# 06-LORA.net
KiCad netlist of a schematic drawn in Altium Designer
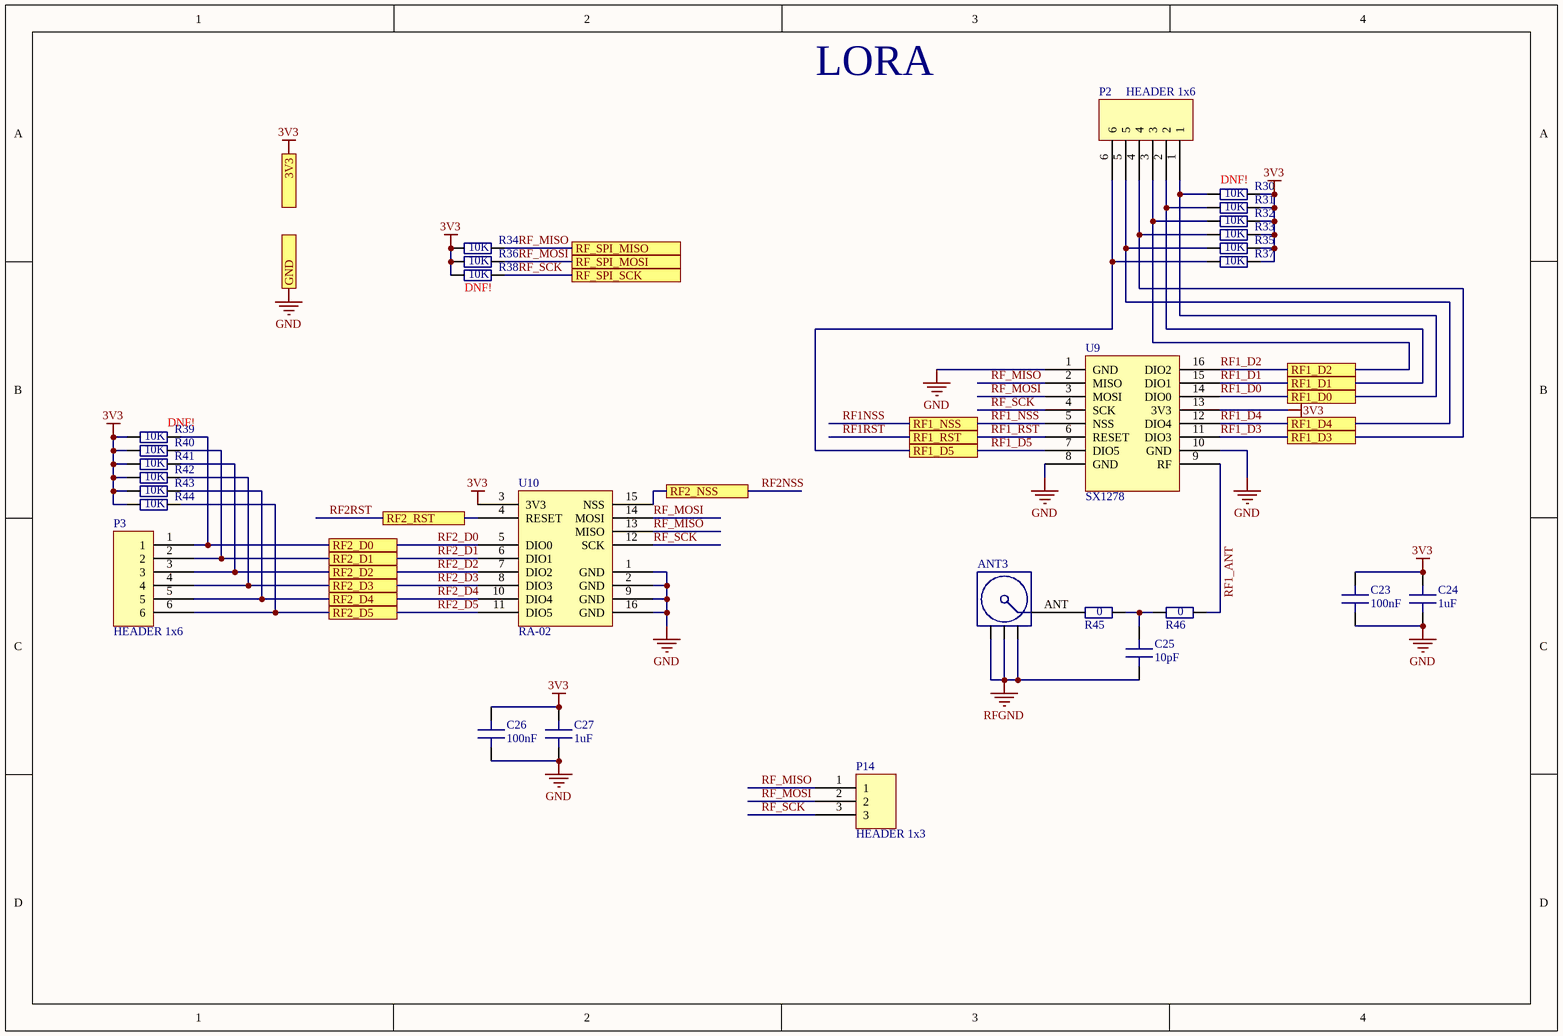
[diagram p0: 06-LORA.SchDoc]

(export (version "E")
  (design (tool "Eeschema 10.0.6"))
  (components
    (comp (ref "ANT3")
      (value "UFL")
      (footprint "U.FL CONNECTOR")
      (description "Generic U.FL connector with 1 ANT + 3 GND")
      (libsource (lib "ComponentsLib") (part "ANT-U.FL"))
    )
    (comp (ref "C23")
      (value "100nF")
      (footprint "C0603")
      (description "Ceramic capacitor")
      (fields (field (name "VOLTAGE") "16V"))
      (libsource (lib "A.Shelestov_Capacitors") (part "C0603_100nF_16V"))
    )
    (comp (ref "C24")
      (value "1uF")
      (footprint "C0805")
      (description "Ceramic capacitor")
      (fields (field (name "VOLTAGE") "25V"))
      (libsource (lib "A.Shelestov_Capacitors") (part "C0805_1uF_25V"))
    )
    (comp (ref "C25")
      (value "10pF")
      (footprint "C0402")
      (description "Ceramic capacitor")
      (fields (field (name "VOLTAGE") "50V"))
      (libsource (lib "A.Shelestov_Capacitors") (part "C0402_10pF_50V"))
    )
    (comp (ref "C26")
      (value "100nF")
      (footprint "C0603")
      (description "Ceramic capacitor")
      (fields (field (name "VOLTAGE") "16V"))
      (libsource (lib "A.Shelestov_Capacitors") (part "C0603_100nF_16V"))
    )
    (comp (ref "C27")
      (value "1uF")
      (footprint "C0805")
      (description "Ceramic capacitor")
      (fields (field (name "VOLTAGE") "25V"))
      (libsource (lib "A.Shelestov_Capacitors") (part "C0805_1uF_25V"))
    )
    (comp (ref "P2")
      (value "HEADER 1x6")
      (footprint "HEADER 1x6 2.54")
      (libsource (lib "ComponentsLib") (part "HEADER 1x6"))
    )
    (comp (ref "P3")
      (value "HEADER 1x6")
      (footprint "HEADER 1x6 2.54")
      (libsource (lib "") (part "HEADER 1x6_1"))
    )
    (comp (ref "P14")
      (value "HEADER 1x3")
      (footprint "UART_2.54")
      (libsource (lib "ComponentsLib") (part "HEADER 1x3"))
    )
    (comp (ref "R30")
      (value "~")
      (footprint "R0603")
      (description "Resistor General")
      (fields (field (name "TOLERANCE") "5%") (field (name "RESISTANCE") "10K"))
      (libsource (lib "A.Shelestov_Resistors") (part "R0603_10K"))
    )
    (comp (ref "R31")
      (value "~")
      (footprint "R0603")
      (description "Resistor General")
      (fields (field (name "TOLERANCE") "5%") (field (name "RESISTANCE") "10K"))
      (libsource (lib "A.Shelestov_Resistors") (part "R0603_10K"))
    )
    (comp (ref "R32")
      (value "~")
      (footprint "R0603")
      (description "Resistor General")
      (fields (field (name "TOLERANCE") "5%") (field (name "RESISTANCE") "10K"))
      (libsource (lib "A.Shelestov_Resistors") (part "R0603_10K"))
    )
    (comp (ref "R33")
      (value "~")
      (footprint "R0603")
      (description "Resistor General")
      (fields (field (name "TOLERANCE") "5%") (field (name "RESISTANCE") "10K"))
      (libsource (lib "A.Shelestov_Resistors") (part "R0603_10K"))
    )
    (comp (ref "R34")
      (value "~")
      (footprint "R0603")
      (description "Resistor General")
      (fields (field (name "TOLERANCE") "5%") (field (name "RESISTANCE") "10K"))
      (libsource (lib "A.Shelestov_Resistors") (part "R0603_10K"))
    )
    (comp (ref "R35")
      (value "~")
      (footprint "R0603")
      (description "Resistor General")
      (fields (field (name "TOLERANCE") "5%") (field (name "RESISTANCE") "10K"))
      (libsource (lib "A.Shelestov_Resistors") (part "R0603_10K"))
    )
    (comp (ref "R36")
      (value "~")
      (footprint "R0603")
      (description "Resistor General")
      (fields (field (name "TOLERANCE") "5%") (field (name "RESISTANCE") "10K"))
      (libsource (lib "A.Shelestov_Resistors") (part "R0603_10K"))
    )
    (comp (ref "R37")
      (value "~")
      (footprint "R0603")
      (description "Resistor General")
      (fields (field (name "TOLERANCE") "5%") (field (name "RESISTANCE") "10K"))
      (libsource (lib "A.Shelestov_Resistors") (part "R0603_10K"))
    )
    (comp (ref "R38")
      (value "~")
      (footprint "R0603")
      (description "Resistor General")
      (fields (field (name "TOLERANCE") "5%") (field (name "RESISTANCE") "10K"))
      (libsource (lib "A.Shelestov_Resistors") (part "R0603_10K"))
    )
    (comp (ref "R39")
      (value "~")
      (footprint "R0603")
      (description "Resistor General")
      (fields (field (name "TOLERANCE") "5%") (field (name "RESISTANCE") "10K"))
      (libsource (lib "A.Shelestov_Resistors") (part "R0603_10K"))
    )
    (comp (ref "R40")
      (value "~")
      (footprint "R0603")
      (description "Resistor General")
      (fields (field (name "TOLERANCE") "5%") (field (name "RESISTANCE") "10K"))
      (libsource (lib "A.Shelestov_Resistors") (part "R0603_10K"))
    )
    (comp (ref "R41")
      (value "~")
      (footprint "R0603")
      (description "Resistor General")
      (fields (field (name "TOLERANCE") "5%") (field (name "RESISTANCE") "10K"))
      (libsource (lib "A.Shelestov_Resistors") (part "R0603_10K"))
    )
    (comp (ref "R42")
      (value "~")
      (footprint "R0603")
      (description "Resistor General")
      (fields (field (name "TOLERANCE") "5%") (field (name "RESISTANCE") "10K"))
      (libsource (lib "A.Shelestov_Resistors") (part "R0603_10K"))
    )
    (comp (ref "R43")
      (value "~")
      (footprint "R0603")
      (description "Resistor General")
      (fields (field (name "TOLERANCE") "5%") (field (name "RESISTANCE") "10K"))
      (libsource (lib "A.Shelestov_Resistors") (part "R0603_10K"))
    )
    (comp (ref "R44")
      (value "~")
      (footprint "R0603")
      (description "Resistor General")
      (fields (field (name "TOLERANCE") "5%") (field (name "RESISTANCE") "10K"))
      (libsource (lib "A.Shelestov_Resistors") (part "R0603_10K"))
    )
    (comp (ref "R45")
      (value "~")
      (footprint "R0402")
      (description "Resistor General")
      (fields (field (name "RESISTANCE") "0"))
      (libsource (lib "A.Shelestov_Resistors") (part "R0402_0R"))
    )
    (comp (ref "R46")
      (value "~")
      (footprint "R0402")
      (description "Resistor General")
      (fields (field (name "RESISTANCE") "0"))
      (libsource (lib "A.Shelestov_Resistors") (part "R0402_0R"))
    )
    (comp (ref "U9")
      (value "SX1278")
      (footprint "SX1278")
      (description "SX1278 LoRa modem")
      (libsource (lib "ComponentsLib") (part "SX1278"))
    )
    (comp (ref "U10")
      (value "RA-02")
      (footprint "RA-02")
      (description "RA-02 LoRa modem by Ai-Thinker")
      (libsource (lib "ComponentsLib") (part "RA-02"))
    )
  )
  (nets
    (net (code "1") (name "/RF1NSS") (class "Default")
      (node (ref "U9") (pin "5") (pinfunction "NSS_5") (pintype "passive"))
    )
    (net (code "2") (name "/RF1RST") (class "Default")
      (node (ref "U9") (pin "6") (pinfunction "RESET_6") (pintype "passive"))
    )
    (net (code "3") (name "/RF1_ANT") (class "Default")
      (node (ref "R46") (pin "2") (pinfunction "2_2") (pintype "passive"))
      (node (ref "U9") (pin "9") (pinfunction "RF_9") (pintype "passive"))
    )
    (net (code "4") (name "/RF1_D0") (class "Default")
      (node (ref "P2") (pin "1") (pinfunction "1_1") (pintype "passive"))
      (node (ref "R30") (pin "1") (pinfunction "1_1") (pintype "passive"))
      (node (ref "U9") (pin "14") (pinfunction "DIO0_14") (pintype "passive"))
    )
    (net (code "5") (name "/RF1_D1") (class "Default")
      (node (ref "P2") (pin "2") (pinfunction "2_2") (pintype "passive"))
      (node (ref "R31") (pin "1") (pinfunction "1_1") (pintype "passive"))
      (node (ref "U9") (pin "15") (pinfunction "DIO1_15") (pintype "passive"))
    )
    (net (code "6") (name "/RF1_D2") (class "Default")
      (node (ref "P2") (pin "3") (pinfunction "3_3") (pintype "passive"))
      (node (ref "R32") (pin "1") (pinfunction "1_1") (pintype "passive"))
      (node (ref "U9") (pin "16") (pinfunction "DIO2_16") (pintype "passive"))
    )
    (net (code "7") (name "/RF1_D3") (class "Default")
      (node (ref "P2") (pin "4") (pinfunction "4_4") (pintype "passive"))
      (node (ref "R33") (pin "1") (pinfunction "1_1") (pintype "passive"))
      (node (ref "U9") (pin "11") (pinfunction "DIO3_11") (pintype "passive"))
    )
    (net (code "8") (name "/RF1_D4") (class "Default")
      (node (ref "P2") (pin "5") (pinfunction "5_5") (pintype "passive"))
      (node (ref "R35") (pin "1") (pinfunction "1_1") (pintype "passive"))
      (node (ref "U9") (pin "12") (pinfunction "DIO4_12") (pintype "passive"))
    )
    (net (code "9") (name "/RF1_D5") (class "Default")
      (node (ref "P2") (pin "6") (pinfunction "6_6") (pintype "passive"))
      (node (ref "R37") (pin "1") (pinfunction "1_1") (pintype "passive"))
      (node (ref "U9") (pin "7") (pinfunction "DIO5_7") (pintype "passive"))
    )
    (net (code "10") (name "/RF2NSS") (class "Default")
      (node (ref "U10") (pin "15") (pinfunction "NSS_15") (pintype "passive"))
    )
    (net (code "11") (name "/RF2RST") (class "Default")
      (node (ref "U10") (pin "4") (pinfunction "RESET_4") (pintype "passive"))
    )
    (net (code "12") (name "/RF2_D0") (class "Default")
      (node (ref "P3") (pin "1") (pinfunction "1_1") (pintype "passive"))
      (node (ref "R39") (pin "2") (pinfunction "2_2") (pintype "passive"))
      (node (ref "U10") (pin "5") (pinfunction "DIO0_5") (pintype "passive"))
    )
    (net (code "13") (name "/RF2_D1") (class "Default")
      (node (ref "P3") (pin "2") (pinfunction "2_2") (pintype "passive"))
      (node (ref "R40") (pin "2") (pinfunction "2_2") (pintype "passive"))
      (node (ref "U10") (pin "6") (pinfunction "DIO1_6") (pintype "passive"))
    )
    (net (code "14") (name "/RF2_D2") (class "Default")
      (node (ref "P3") (pin "3") (pinfunction "3_3") (pintype "passive"))
      (node (ref "R41") (pin "2") (pinfunction "2_2") (pintype "passive"))
      (node (ref "U10") (pin "7") (pinfunction "DIO2_7") (pintype "passive"))
    )
    (net (code "15") (name "/RF2_D3") (class "Default")
      (node (ref "P3") (pin "4") (pinfunction "4_4") (pintype "passive"))
      (node (ref "R42") (pin "2") (pinfunction "2_2") (pintype "passive"))
      (node (ref "U10") (pin "8") (pinfunction "DIO3_8") (pintype "passive"))
    )
    (net (code "16") (name "/RF2_D4") (class "Default")
      (node (ref "P3") (pin "5") (pinfunction "5_5") (pintype "passive"))
      (node (ref "R43") (pin "2") (pinfunction "2_2") (pintype "passive"))
      (node (ref "U10") (pin "10") (pinfunction "DIO4_10") (pintype "passive"))
    )
    (net (code "17") (name "/RF2_D5") (class "Default")
      (node (ref "P3") (pin "6") (pinfunction "6_6") (pintype "passive"))
      (node (ref "R44") (pin "2") (pinfunction "2_2") (pintype "passive"))
      (node (ref "U10") (pin "11") (pinfunction "DIO5_11") (pintype "passive"))
    )
    (net (code "18") (name "/RF_MISO") (class "Default")
      (node (ref "P14") (pin "1") (pinfunction "1_1") (pintype "passive"))
      (node (ref "R34") (pin "2") (pinfunction "2_2") (pintype "passive"))
      (node (ref "U10") (pin "13") (pinfunction "MISO_13") (pintype "passive"))
      (node (ref "U9") (pin "2") (pinfunction "MISO_2") (pintype "passive"))
    )
    (net (code "19") (name "/RF_MOSI") (class "Default")
      (node (ref "P14") (pin "2") (pinfunction "2_2") (pintype "passive"))
      (node (ref "R36") (pin "2") (pinfunction "2_2") (pintype "passive"))
      (node (ref "U10") (pin "14") (pinfunction "MOSI_14") (pintype "passive"))
      (node (ref "U9") (pin "3") (pinfunction "MOSI_3") (pintype "passive"))
    )
    (net (code "20") (name "/RF_SCK") (class "Default")
      (node (ref "P14") (pin "3") (pinfunction "3_3") (pintype "passive"))
      (node (ref "R38") (pin "2") (pinfunction "2_2") (pintype "passive"))
      (node (ref "U10") (pin "12") (pinfunction "SCK_12") (pintype "passive"))
      (node (ref "U9") (pin "4") (pinfunction "SCK_4") (pintype "passive"))
    )
    (net (code "21") (name "3V3") (class "Default")
      (node (ref "C23") (pin "2") (pinfunction "2_2") (pintype "passive"))
      (node (ref "C24") (pin "2") (pinfunction "2_2") (pintype "passive"))
      (node (ref "C26") (pin "2") (pinfunction "2_2") (pintype "passive"))
      (node (ref "C27") (pin "2") (pinfunction "2_2") (pintype "passive"))
      (node (ref "R30") (pin "2") (pinfunction "2_2") (pintype "passive"))
      (node (ref "R31") (pin "2") (pinfunction "2_2") (pintype "passive"))
      (node (ref "R32") (pin "2") (pinfunction "2_2") (pintype "passive"))
      (node (ref "R33") (pin "2") (pinfunction "2_2") (pintype "passive"))
      (node (ref "R34") (pin "1") (pinfunction "1_1") (pintype "passive"))
      (node (ref "R35") (pin "2") (pinfunction "2_2") (pintype "passive"))
      (node (ref "R36") (pin "1") (pinfunction "1_1") (pintype "passive"))
      (node (ref "R37") (pin "2") (pinfunction "2_2") (pintype "passive"))
      (node (ref "R38") (pin "1") (pinfunction "1_1") (pintype "passive"))
      (node (ref "R39") (pin "1") (pinfunction "1_1") (pintype "passive"))
      (node (ref "R40") (pin "1") (pinfunction "1_1") (pintype "passive"))
      (node (ref "R41") (pin "1") (pinfunction "1_1") (pintype "passive"))
      (node (ref "R42") (pin "1") (pinfunction "1_1") (pintype "passive"))
      (node (ref "R43") (pin "1") (pinfunction "1_1") (pintype "passive"))
      (node (ref "R44") (pin "1") (pinfunction "1_1") (pintype "passive"))
      (node (ref "U10") (pin "3") (pinfunction "3V3_3") (pintype "passive"))
      (node (ref "U9") (pin "13") (pinfunction "3V3_13") (pintype "passive"))
    )
    (net (code "22") (name "GND") (class "Default")
      (node (ref "C23") (pin "1") (pinfunction "1_1") (pintype "passive"))
      (node (ref "C24") (pin "1") (pinfunction "1_1") (pintype "passive"))
      (node (ref "C26") (pin "1") (pinfunction "1_1") (pintype "passive"))
      (node (ref "C27") (pin "1") (pinfunction "1_1") (pintype "passive"))
      (node (ref "U10") (pin "1") (pinfunction "GND_1") (pintype "passive"))
      (node (ref "U10") (pin "16") (pinfunction "GND_16") (pintype "passive"))
      (node (ref "U10") (pin "2") (pinfunction "GND_2") (pintype "passive"))
      (node (ref "U10") (pin "9") (pinfunction "GND_9") (pintype "passive"))
      (node (ref "U9") (pin "1") (pinfunction "GND_1") (pintype "passive"))
      (node (ref "U9") (pin "10") (pinfunction "GND_10") (pintype "passive"))
      (node (ref "U9") (pin "8") (pinfunction "GND_8") (pintype "passive"))
    )
    (net (code "23") (name "Net-(ANT3-SIGNAL)") (class "Default")
      (node (ref "ANT3") (pin "ANT") (pinfunction "SIGNAL_ANT") (pintype "passive"))
      (node (ref "R45") (pin "1") (pinfunction "1_1") (pintype "passive"))
    )
    (net (code "24") (name "Net-(C25-Pad2)") (class "Default")
      (node (ref "C25") (pin "2") (pinfunction "2_2") (pintype "passive"))
      (node (ref "R45") (pin "2") (pinfunction "2_2") (pintype "passive"))
      (node (ref "R46") (pin "1") (pinfunction "1_1") (pintype "passive"))
    )
    (net (code "25") (name "RFGND") (class "Default")
      (node (ref "ANT3") (pin "GND") (pinfunction "GND_GND") (pintype "passive"))
      (node (ref "C25") (pin "1") (pinfunction "1_1") (pintype "passive"))
    )
  )
)
